# CP100-_5V1A__V1_0.net
KiCad netlist of a schematic drawn in Altium Designer
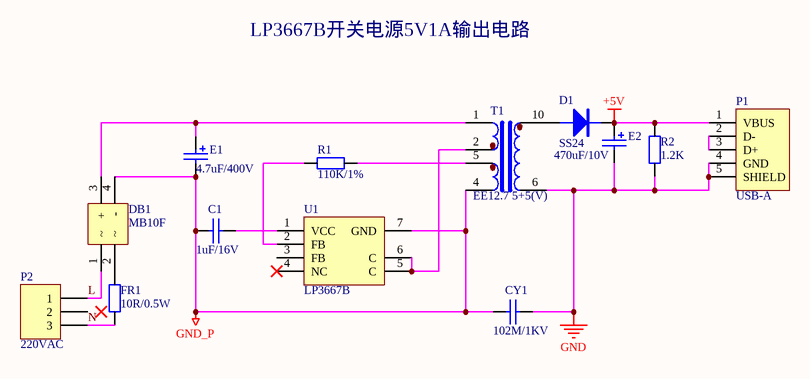
[diagram p0: CP100-(5V1A)_V1.0.SchDoc]

(export (version "E")
  (design (tool "Eeschema 10.0.6"))
  (components
    (comp (ref "C1")
      (value "1uF/16V")
      (footprint "Cheng_Resistor_Capacitor:0805_C")
      (libsource (lib "Cheng_Resistor_Capacitor") (part "Cap1"))
    )
    (comp (ref "CY1")
      (value "102M/1KV")
      (footprint "Cheng_Resistor_Capacitor:CY-5MM")
      (libsource (lib "Cheng_Resistor_Capacitor") (part "Cap1"))
    )
    (comp (ref "D1")
      (value "SS24")
      (footprint "Cheng_Diode_Transistor:DO-214AC(SMA)")
      (description "SS14,SS24,SS34,M7")
      (libsource (lib "Cheng_Diode_Transistor") (part "Diode-A"))
    )
    (comp (ref "DB1")
      (value "MB10F")
      (footprint "Cheng_Diode_Transistor:MB10F")
      (libsource (lib "Cheng_Diode_Transistor") (part "MB10F"))
    )
    (comp (ref "E1")
      (value "4.7uF/400V")
      (footprint "Cheng_Resistor_Capacitor:CS_220uF/25V")
      (libsource (lib "Cheng_Resistor_Capacitor") (part "Cap Pol1"))
    )
    (comp (ref "E2")
      (value "470uF/10V")
      (footprint "Cheng_Resistor_Capacitor:CS_470uF/16V")
      (libsource (lib "Cheng_Resistor_Capacitor") (part "Cap Pol1"))
    )
    (comp (ref "FR1")
      (value "10R/0.5W")
      (footprint "Cheng_Resistor_Capacitor:R0.12L")
      (libsource (lib "") (part "Res1_1"))
    )
    (comp (ref "P1")
      (value "USB-A")
      (footprint "Cheng_Interface Unit:USB-AF10.6/90")
      (libsource (lib "Cheng_Interface Unit") (part "USB-A"))
    )
    (comp (ref "P2")
      (value "220VAC")
      (footprint "Cheng_Interface Unit:KF5.08-3P")
      (description "Header, 3-Pin")
      (fields (field (name "PUBLISHER") "Altium Limited"))
      (libsource (lib "Cheng_Interface Unit") (part "Header 3"))
    )
    (comp (ref "R1")
      (value "110K/1%")
      (footprint "Cheng_Resistor_Capacitor:0603_RN")
      (libsource (lib "Cheng_Resistor_Capacitor") (part "Res1"))
    )
    (comp (ref "R2")
      (value "1.2K")
      (footprint "Cheng_Resistor_Capacitor:0805_R")
      (libsource (lib "") (part "Res1_2"))
    )
    (comp (ref "T1")
      (value "EE12.7 5+5(V)")
      (footprint "CP100-(5V1A)_Weld_V1.0:EE12.7 5+5(V)")
      (libsource (lib "CP100-(5V1A)_V1.0") (part "EE12.7 5+5(V)"))
    )
    (comp (ref "U1")
      (value "LP3667B")
      (footprint "Cheng_Manostat:SOP7")
      (description "LP3667A, LP3667B, LP3667AH, LP3667BH")
      (libsource (lib "Cheng_Manostat") (part "LP3667B"))
    )
  )
  (nets
    (net (code "1") (name "+5V") (class "Default")
      (node (ref "D1") (pin "K") (pinfunction "2_K") (pintype "passive"))
      (node (ref "E2") (pin "1") (pinfunction "1_1") (pintype "passive"))
      (node (ref "P1") (pin "1") (pinfunction "VBUS_1") (pintype "passive"))
      (node (ref "R2") (pin "2") (pinfunction "2_2") (pintype "passive"))
    )
    (net (code "2") (name "/L") (class "Default")
      (node (ref "DB1") (pin "1") (pinfunction "~_1") (pintype "passive"))
      (node (ref "P2") (pin "1") (pinfunction "1_1") (pintype "passive"))
    )
    (net (code "3") (name "/N") (class "Default")
      (node (ref "FR1") (pin "2") (pinfunction "2_2") (pintype "passive"))
      (node (ref "P2") (pin "3") (pinfunction "3_3") (pintype "passive"))
    )
    (net (code "4") (name "GND") (class "Default")
      (node (ref "CY1") (pin "2") (pinfunction "2_2") (pintype "passive"))
      (node (ref "E2") (pin "2") (pinfunction "2_2") (pintype "passive"))
      (node (ref "P1") (pin "4") (pinfunction "GND_4") (pintype "passive"))
      (node (ref "P1") (pin "5") (pinfunction "SHIELD_5") (pintype "passive"))
      (node (ref "R2") (pin "1") (pinfunction "1_1") (pintype "passive"))
      (node (ref "T1") (pin "6") (pinfunction "Ns_6") (pintype "passive"))
    )
    (net (code "5") (name "GND_P") (class "Default")
      (node (ref "C1") (pin "2") (pinfunction "2_2") (pintype "passive"))
      (node (ref "CY1") (pin "1") (pinfunction "1_1") (pintype "passive"))
      (node (ref "DB1") (pin "4") (pinfunction "-_4") (pintype "passive"))
      (node (ref "E1") (pin "2") (pinfunction "2_2") (pintype "passive"))
      (node (ref "T1") (pin "4") (pinfunction "Nd_4") (pintype "passive"))
      (node (ref "U1") (pin "7") (pinfunction "GND_7") (pintype "passive"))
    )
    (net (code "6") (name "Net-(D1-1)") (class "Default")
      (node (ref "D1") (pin "A") (pinfunction "1_A") (pintype "passive"))
      (node (ref "T1") (pin "10") (pinfunction "Ns_10") (pintype "passive"))
    )
    (net (code "7") (name "Net-(DB1-+)") (class "Default")
      (node (ref "DB1") (pin "3") (pinfunction "+_3") (pintype "passive"))
      (node (ref "E1") (pin "1") (pinfunction "1_1") (pintype "passive"))
      (node (ref "T1") (pin "1") (pinfunction "Np_1") (pintype "passive"))
    )
    (net (code "8") (name "Net-(DB1-~-Pad2)") (class "Default")
      (node (ref "DB1") (pin "2") (pinfunction "~_2") (pintype "passive"))
      (node (ref "FR1") (pin "1") (pinfunction "1_1") (pintype "passive"))
    )
    (net (code "9") (name "Net-(P1-D+)") (class "Default")
      (node (ref "P1") (pin "2") (pinfunction "D-_2") (pintype "passive"))
      (node (ref "P1") (pin "3") (pinfunction "D+_3") (pintype "passive"))
    )
    (net (code "10") (name "Net-(R1-Pad1)") (class "Default")
      (node (ref "R1") (pin "1") (pinfunction "1_1") (pintype "passive"))
      (node (ref "U1") (pin "2") (pinfunction "FB_2") (pintype "passive"))
    )
    (net (code "11") (name "Net-(R1-Pad2)") (class "Default")
      (node (ref "R1") (pin "2") (pinfunction "2_2") (pintype "passive"))
      (node (ref "T1") (pin "5") (pinfunction "Nd_5") (pintype "passive"))
    )
    (net (code "12") (name "Net-(T1-Np-Pad2)") (class "Default")
      (node (ref "T1") (pin "2") (pinfunction "Np_2") (pintype "passive"))
      (node (ref "U1") (pin "5") (pinfunction "C_5") (pintype "passive"))
      (node (ref "U1") (pin "6") (pinfunction "C_6") (pintype "passive"))
    )
    (net (code "13") (name "Net-(U1-VCC)") (class "Default")
      (node (ref "C1") (pin "1") (pinfunction "1_1") (pintype "passive"))
      (node (ref "U1") (pin "1") (pinfunction "VCC_1") (pintype "passive"))
    )
    (net (code "14") (name "unconnected-(P2-Pad2)") (class "Default")
      (node (ref "P2") (pin "2") (pinfunction "2_2") (pintype "passive"))
    )
    (net (code "15") (name "unconnected-(U1-FB-Pad3)") (class "Default")
      (node (ref "U1") (pin "3") (pinfunction "FB_3") (pintype "passive"))
    )
    (net (code "16") (name "unconnected-(U1-NC-Pad4)") (class "Default")
      (node (ref "U1") (pin "4") (pinfunction "NC_4") (pintype "passive+no_connect"))
    )
  )
)
